# roboto.net
KiCad netlist of a schematic drawn in EAGLE
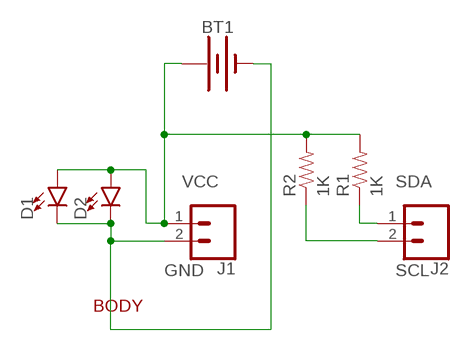
[diagram p0: schematic, sheet 1]

(export (version "E")
  (design (tool "Eeschema 10.0.6"))
  (components
    (comp (ref "BT1")
      (value "BATTERY-20MM_PTH")
      (footprint "eagle-import:BATTCOM_20MM_PTH")
      (libsource (lib "eagle-import") (part "BATTERY-20MM_PTH"))
    )
    (comp (ref "D1")
      (value "LED3MM")
      (footprint "eagle-import:LED_3MM")
      (libsource (lib "eagle-import") (part "LED3MM"))
    )
    (comp (ref "D2")
      (value "LED3MM")
      (footprint "eagle-import:LED_3MM")
      (libsource (lib "eagle-import") (part "LED3MM"))
    )
    (comp (ref "J1")
      (value "CONN_02LOCK")
      (footprint "eagle-import:1X02_LOCK")
      (libsource (lib "eagle-import") (part "CONN_02LOCK"))
    )
    (comp (ref "J2")
      (value "CONN_02LOCK")
      (footprint "eagle-import:1X02_LOCK")
      (libsource (lib "eagle-import") (part "CONN_02LOCK"))
    )
    (comp (ref "R1")
      (value "1K")
      (footprint "eagle-import:AXIAL-0.3EZ")
      (libsource (lib "eagle-import") (part "1KOHM-1/4W-1%(PTH)HORIZ-KIT"))
    )
    (comp (ref "R2")
      (value "1K")
      (footprint "eagle-import:AXIAL-0.3EZ")
      (libsource (lib "eagle-import") (part "1KOHM-1/4W-1%(PTH)HORIZ-KIT"))
    )
    (comp (ref "U$1")
      (value "BODYROBOTO")
      (footprint "eagle-import:ROBOTO")
      (libsource (lib "eagle-import") (part "BODYROBOTO"))
    )
  )
  (nets
    (net (code "1") (name "/GND") (class "Default")
      (node (ref "BT1") (pin "2") (pinfunction "-_2") (pintype "power_in"))
      (node (ref "D1") (pin "K") (pinfunction "C_K") (pintype "passive"))
      (node (ref "D2") (pin "K") (pinfunction "C_K") (pintype "passive"))
      (node (ref "J1") (pin "2") (pinfunction "2_2") (pintype "passive"))
    )
    (net (code "2") (name "/SCL") (class "Default")
      (node (ref "J2") (pin "2") (pinfunction "2_2") (pintype "passive"))
      (node (ref "R2") (pin "P$1") (pinfunction "1_P$1") (pintype "passive"))
    )
    (net (code "3") (name "/SDA") (class "Default")
      (node (ref "J2") (pin "1") (pinfunction "1_1") (pintype "passive"))
      (node (ref "R1") (pin "P$1") (pinfunction "1_P$1") (pintype "passive"))
    )
    (net (code "4") (name "/VCC") (class "Default")
      (node (ref "BT1") (pin "1") (pinfunction "+_1") (pintype "power_in"))
      (node (ref "D1") (pin "A") (pinfunction "A_A") (pintype "passive"))
      (node (ref "D2") (pin "A") (pinfunction "A_A") (pintype "passive"))
      (node (ref "J1") (pin "1") (pinfunction "1_1") (pintype "passive"))
      (node (ref "R1") (pin "P$2") (pinfunction "2_P$2") (pintype "passive"))
      (node (ref "R2") (pin "P$2") (pinfunction "2_P$2") (pintype "passive"))
    )
  )
)
